# Mezz1.net
KiCad netlist of a schematic drawn in Altium Designer
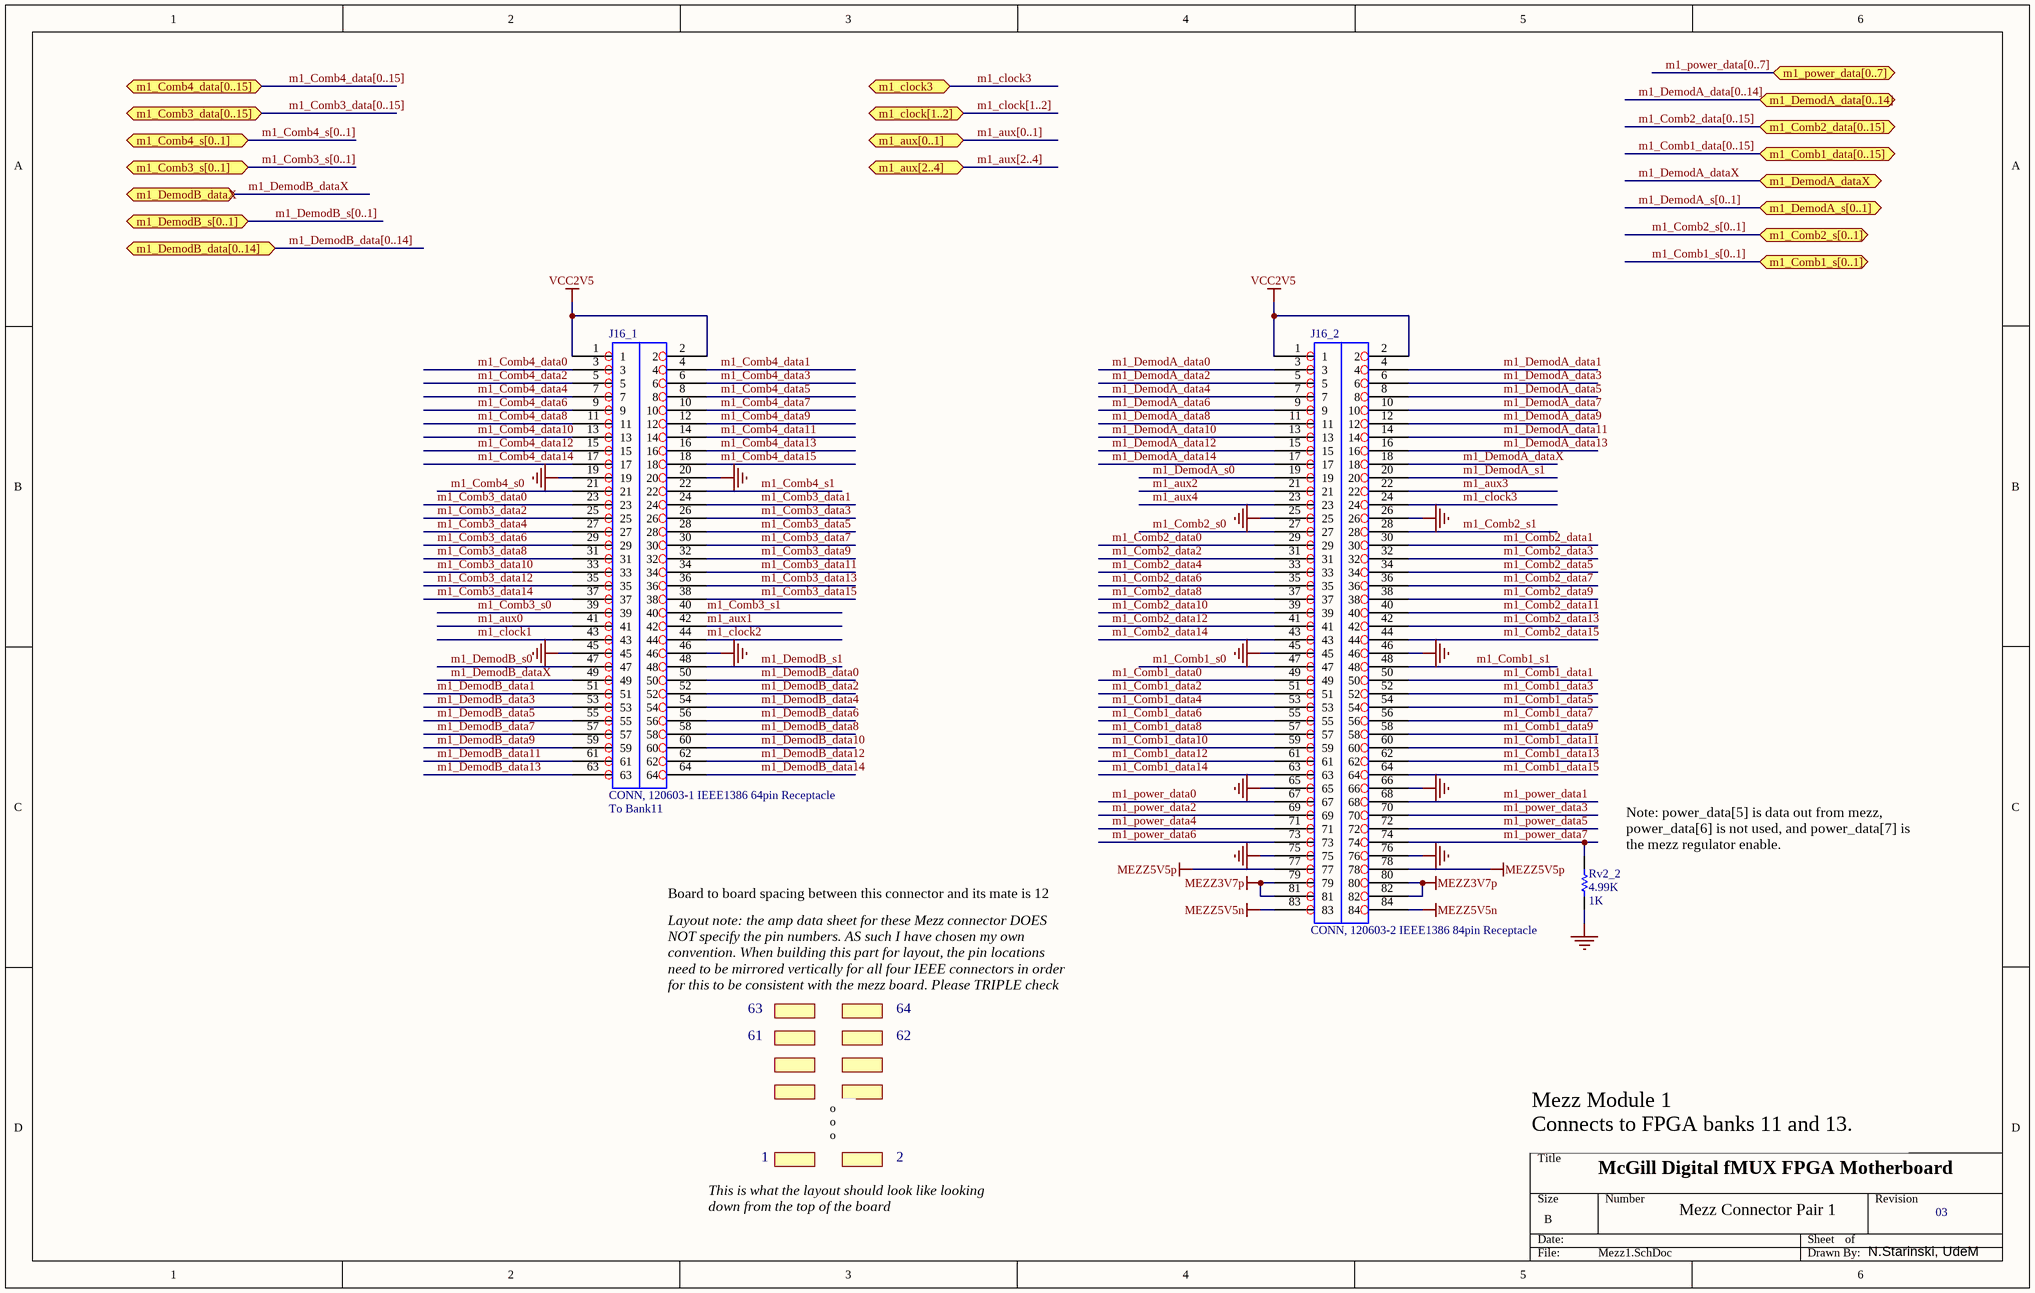
[diagram p0: Mezz1.SchDoc]

(export (version "E")
  (design (tool "Eeschema 10.0.6"))
  (components
    (comp (ref "J16_1")
      (value "CONN, 120603-1 IEEE1386 64pin Receptacle")
      (footprint "120603-1")
      (description "1.0mm FH (IEEE1386) 64-pin Connector")
      (fields (field (name "RELATION") "To Bank11"))
      (libsource (lib "IEEE1386") (part "120603-1"))
    )
    (comp (ref "J16_2")
      (value "CONN, 120603-2 IEEE1386 84pin Receptacle")
      (footprint "120603-2")
      (description "1.0mm FH (IEEE1386) 84-pin Connector")
      (libsource (lib "IEEE1386") (part "120603-2"))
    )
    (comp (ref "Rv2_2")
      (value "4.99K")
      (footprint "1608[0603]")
      (description "Semiconductor Resistor")
      (fields (field (name "ALTIUM_VALUE") "1K") (field (name "PUBLISHER") "Altium Limited"))
      (libsource (lib "Miscellaneous Devices") (part "Res Semi"))
    )
  )
  (nets
    (net (code "1") (name "/m1_Comb1_data0") (class "Default")
      (node (ref "J16_2") (pin "49") (pinfunction "49_49") (pintype "passive"))
    )
    (net (code "2") (name "/m1_Comb1_data1") (class "Default")
      (node (ref "J16_2") (pin "50") (pinfunction "50_50") (pintype "passive"))
    )
    (net (code "3") (name "/m1_Comb1_data2") (class "Default")
      (node (ref "J16_2") (pin "51") (pinfunction "51_51") (pintype "passive"))
    )
    (net (code "4") (name "/m1_Comb1_data3") (class "Default")
      (node (ref "J16_2") (pin "52") (pinfunction "52_52") (pintype "passive"))
    )
    (net (code "5") (name "/m1_Comb1_data4") (class "Default")
      (node (ref "J16_2") (pin "53") (pinfunction "53_53") (pintype "passive"))
    )
    (net (code "6") (name "/m1_Comb1_data5") (class "Default")
      (node (ref "J16_2") (pin "54") (pinfunction "54_54") (pintype "passive"))
    )
    (net (code "7") (name "/m1_Comb1_data6") (class "Default")
      (node (ref "J16_2") (pin "55") (pinfunction "55_55") (pintype "passive"))
    )
    (net (code "8") (name "/m1_Comb1_data7") (class "Default")
      (node (ref "J16_2") (pin "56") (pinfunction "56_56") (pintype "passive"))
    )
    (net (code "9") (name "/m1_Comb1_data8") (class "Default")
      (node (ref "J16_2") (pin "57") (pinfunction "57_57") (pintype "passive"))
    )
    (net (code "10") (name "/m1_Comb1_data9") (class "Default")
      (node (ref "J16_2") (pin "58") (pinfunction "58_58") (pintype "passive"))
    )
    (net (code "11") (name "/m1_Comb1_data10") (class "Default")
      (node (ref "J16_2") (pin "59") (pinfunction "59_59") (pintype "passive"))
    )
    (net (code "12") (name "/m1_Comb1_data11") (class "Default")
      (node (ref "J16_2") (pin "60") (pinfunction "60_60") (pintype "passive"))
    )
    (net (code "13") (name "/m1_Comb1_data12") (class "Default")
      (node (ref "J16_2") (pin "61") (pinfunction "61_61") (pintype "passive"))
    )
    (net (code "14") (name "/m1_Comb1_data13") (class "Default")
      (node (ref "J16_2") (pin "62") (pinfunction "62_62") (pintype "passive"))
    )
    (net (code "15") (name "/m1_Comb1_data14") (class "Default")
      (node (ref "J16_2") (pin "63") (pinfunction "63_63") (pintype "passive"))
    )
    (net (code "16") (name "/m1_Comb1_data15") (class "Default")
      (node (ref "J16_2") (pin "64") (pinfunction "64_64") (pintype "passive"))
    )
    (net (code "18") (name "/m1_Comb1_s0") (class "Default")
      (node (ref "J16_2") (pin "47") (pinfunction "47_47") (pintype "passive"))
    )
    (net (code "19") (name "/m1_Comb1_s1") (class "Default")
      (node (ref "J16_2") (pin "48") (pinfunction "48_48") (pintype "passive"))
    )
    (net (code "21") (name "/m1_Comb2_data0") (class "Default")
      (node (ref "J16_2") (pin "29") (pinfunction "29_29") (pintype "passive"))
    )
    (net (code "22") (name "/m1_Comb2_data1") (class "Default")
      (node (ref "J16_2") (pin "30") (pinfunction "30_30") (pintype "passive"))
    )
    (net (code "23") (name "/m1_Comb2_data2") (class "Default")
      (node (ref "J16_2") (pin "31") (pinfunction "31_31") (pintype "passive"))
    )
    (net (code "24") (name "/m1_Comb2_data3") (class "Default")
      (node (ref "J16_2") (pin "32") (pinfunction "32_32") (pintype "passive"))
    )
    (net (code "25") (name "/m1_Comb2_data4") (class "Default")
      (node (ref "J16_2") (pin "33") (pinfunction "33_33") (pintype "passive"))
    )
    (net (code "26") (name "/m1_Comb2_data5") (class "Default")
      (node (ref "J16_2") (pin "34") (pinfunction "34_34") (pintype "passive"))
    )
    (net (code "27") (name "/m1_Comb2_data6") (class "Default")
      (node (ref "J16_2") (pin "35") (pinfunction "35_35") (pintype "passive"))
    )
    (net (code "28") (name "/m1_Comb2_data7") (class "Default")
      (node (ref "J16_2") (pin "36") (pinfunction "36_36") (pintype "passive"))
    )
    (net (code "29") (name "/m1_Comb2_data8") (class "Default")
      (node (ref "J16_2") (pin "37") (pinfunction "37_37") (pintype "passive"))
    )
    (net (code "30") (name "/m1_Comb2_data9") (class "Default")
      (node (ref "J16_2") (pin "38") (pinfunction "38_38") (pintype "passive"))
    )
    (net (code "31") (name "/m1_Comb2_data10") (class "Default")
      (node (ref "J16_2") (pin "39") (pinfunction "39_39") (pintype "passive"))
    )
    (net (code "32") (name "/m1_Comb2_data11") (class "Default")
      (node (ref "J16_2") (pin "40") (pinfunction "40_40") (pintype "passive"))
    )
    (net (code "33") (name "/m1_Comb2_data12") (class "Default")
      (node (ref "J16_2") (pin "41") (pinfunction "41_41") (pintype "passive"))
    )
    (net (code "34") (name "/m1_Comb2_data13") (class "Default")
      (node (ref "J16_2") (pin "42") (pinfunction "42_42") (pintype "passive"))
    )
    (net (code "35") (name "/m1_Comb2_data14") (class "Default")
      (node (ref "J16_2") (pin "43") (pinfunction "43_43") (pintype "passive"))
    )
    (net (code "36") (name "/m1_Comb2_data15") (class "Default")
      (node (ref "J16_2") (pin "44") (pinfunction "44_44") (pintype "passive"))
    )
    (net (code "38") (name "/m1_Comb2_s0") (class "Default")
      (node (ref "J16_2") (pin "27") (pinfunction "27_27") (pintype "passive"))
    )
    (net (code "39") (name "/m1_Comb2_s1") (class "Default")
      (node (ref "J16_2") (pin "28") (pinfunction "28_28") (pintype "passive"))
    )
    (net (code "41") (name "/m1_Comb3_data0") (class "Default")
      (node (ref "J16_1") (pin "23") (pinfunction "23_23") (pintype "passive"))
    )
    (net (code "42") (name "/m1_Comb3_data1") (class "Default")
      (node (ref "J16_1") (pin "24") (pinfunction "24_24") (pintype "passive"))
    )
    (net (code "43") (name "/m1_Comb3_data2") (class "Default")
      (node (ref "J16_1") (pin "25") (pinfunction "25_25") (pintype "passive"))
    )
    (net (code "44") (name "/m1_Comb3_data3") (class "Default")
      (node (ref "J16_1") (pin "26") (pinfunction "26_26") (pintype "passive"))
    )
    (net (code "45") (name "/m1_Comb3_data4") (class "Default")
      (node (ref "J16_1") (pin "27") (pinfunction "27_27") (pintype "passive"))
    )
    (net (code "46") (name "/m1_Comb3_data5") (class "Default")
      (node (ref "J16_1") (pin "28") (pinfunction "28_28") (pintype "passive"))
    )
    (net (code "47") (name "/m1_Comb3_data6") (class "Default")
      (node (ref "J16_1") (pin "29") (pinfunction "29_29") (pintype "passive"))
    )
    (net (code "48") (name "/m1_Comb3_data7") (class "Default")
      (node (ref "J16_1") (pin "30") (pinfunction "30_30") (pintype "passive"))
    )
    (net (code "49") (name "/m1_Comb3_data8") (class "Default")
      (node (ref "J16_1") (pin "31") (pinfunction "31_31") (pintype "passive"))
    )
    (net (code "50") (name "/m1_Comb3_data9") (class "Default")
      (node (ref "J16_1") (pin "32") (pinfunction "32_32") (pintype "passive"))
    )
    (net (code "51") (name "/m1_Comb3_data10") (class "Default")
      (node (ref "J16_1") (pin "33") (pinfunction "33_33") (pintype "passive"))
    )
    (net (code "52") (name "/m1_Comb3_data11") (class "Default")
      (node (ref "J16_1") (pin "34") (pinfunction "34_34") (pintype "passive"))
    )
    (net (code "53") (name "/m1_Comb3_data12") (class "Default")
      (node (ref "J16_1") (pin "35") (pinfunction "35_35") (pintype "passive"))
    )
    (net (code "54") (name "/m1_Comb3_data13") (class "Default")
      (node (ref "J16_1") (pin "36") (pinfunction "36_36") (pintype "passive"))
    )
    (net (code "55") (name "/m1_Comb3_data14") (class "Default")
      (node (ref "J16_1") (pin "37") (pinfunction "37_37") (pintype "passive"))
    )
    (net (code "56") (name "/m1_Comb3_data15") (class "Default")
      (node (ref "J16_1") (pin "38") (pinfunction "38_38") (pintype "passive"))
    )
    (net (code "58") (name "/m1_Comb3_s0") (class "Default")
      (node (ref "J16_1") (pin "39") (pinfunction "39_39") (pintype "passive"))
    )
    (net (code "59") (name "/m1_Comb3_s1") (class "Default")
      (node (ref "J16_1") (pin "40") (pinfunction "40_40") (pintype "passive"))
    )
    (net (code "61") (name "/m1_Comb4_data0") (class "Default")
      (node (ref "J16_1") (pin "3") (pinfunction "3_3") (pintype "passive"))
    )
    (net (code "62") (name "/m1_Comb4_data1") (class "Default")
      (node (ref "J16_1") (pin "4") (pinfunction "4_4") (pintype "passive"))
    )
    (net (code "63") (name "/m1_Comb4_data2") (class "Default")
      (node (ref "J16_1") (pin "5") (pinfunction "5_5") (pintype "passive"))
    )
    (net (code "64") (name "/m1_Comb4_data3") (class "Default")
      (node (ref "J16_1") (pin "6") (pinfunction "6_6") (pintype "passive"))
    )
    (net (code "65") (name "/m1_Comb4_data4") (class "Default")
      (node (ref "J16_1") (pin "7") (pinfunction "7_7") (pintype "passive"))
    )
    (net (code "66") (name "/m1_Comb4_data5") (class "Default")
      (node (ref "J16_1") (pin "8") (pinfunction "8_8") (pintype "passive"))
    )
    (net (code "67") (name "/m1_Comb4_data6") (class "Default")
      (node (ref "J16_1") (pin "9") (pinfunction "9_9") (pintype "passive"))
    )
    (net (code "68") (name "/m1_Comb4_data7") (class "Default")
      (node (ref "J16_1") (pin "10") (pinfunction "10_10") (pintype "passive"))
    )
    (net (code "69") (name "/m1_Comb4_data8") (class "Default")
      (node (ref "J16_1") (pin "11") (pinfunction "11_11") (pintype "passive"))
    )
    (net (code "70") (name "/m1_Comb4_data9") (class "Default")
      (node (ref "J16_1") (pin "12") (pinfunction "12_12") (pintype "passive"))
    )
    (net (code "71") (name "/m1_Comb4_data10") (class "Default")
      (node (ref "J16_1") (pin "13") (pinfunction "13_13") (pintype "passive"))
    )
    (net (code "72") (name "/m1_Comb4_data11") (class "Default")
      (node (ref "J16_1") (pin "14") (pinfunction "14_14") (pintype "passive"))
    )
    (net (code "73") (name "/m1_Comb4_data12") (class "Default")
      (node (ref "J16_1") (pin "15") (pinfunction "15_15") (pintype "passive"))
    )
    (net (code "74") (name "/m1_Comb4_data13") (class "Default")
      (node (ref "J16_1") (pin "16") (pinfunction "16_16") (pintype "passive"))
    )
    (net (code "75") (name "/m1_Comb4_data14") (class "Default")
      (node (ref "J16_1") (pin "17") (pinfunction "17_17") (pintype "passive"))
    )
    (net (code "76") (name "/m1_Comb4_data15") (class "Default")
      (node (ref "J16_1") (pin "18") (pinfunction "18_18") (pintype "passive"))
    )
    (net (code "78") (name "/m1_Comb4_s0") (class "Default")
      (node (ref "J16_1") (pin "21") (pinfunction "21_21") (pintype "passive"))
    )
    (net (code "79") (name "/m1_Comb4_s1") (class "Default")
      (node (ref "J16_1") (pin "22") (pinfunction "22_22") (pintype "passive"))
    )
    (net (code "81") (name "/m1_DemodA_data0") (class "Default")
      (node (ref "J16_2") (pin "3") (pinfunction "3_3") (pintype "passive"))
    )
    (net (code "82") (name "/m1_DemodA_data1") (class "Default")
      (node (ref "J16_2") (pin "4") (pinfunction "4_4") (pintype "passive"))
    )
    (net (code "83") (name "/m1_DemodA_data2") (class "Default")
      (node (ref "J16_2") (pin "5") (pinfunction "5_5") (pintype "passive"))
    )
    (net (code "84") (name "/m1_DemodA_data3") (class "Default")
      (node (ref "J16_2") (pin "6") (pinfunction "6_6") (pintype "passive"))
    )
    (net (code "85") (name "/m1_DemodA_data4") (class "Default")
      (node (ref "J16_2") (pin "7") (pinfunction "7_7") (pintype "passive"))
    )
    (net (code "86") (name "/m1_DemodA_data5") (class "Default")
      (node (ref "J16_2") (pin "8") (pinfunction "8_8") (pintype "passive"))
    )
    (net (code "87") (name "/m1_DemodA_data6") (class "Default")
      (node (ref "J16_2") (pin "9") (pinfunction "9_9") (pintype "passive"))
    )
    (net (code "88") (name "/m1_DemodA_data7") (class "Default")
      (node (ref "J16_2") (pin "10") (pinfunction "10_10") (pintype "passive"))
    )
    (net (code "89") (name "/m1_DemodA_data8") (class "Default")
      (node (ref "J16_2") (pin "11") (pinfunction "11_11") (pintype "passive"))
    )
    (net (code "90") (name "/m1_DemodA_data9") (class "Default")
      (node (ref "J16_2") (pin "12") (pinfunction "12_12") (pintype "passive"))
    )
    (net (code "91") (name "/m1_DemodA_data10") (class "Default")
      (node (ref "J16_2") (pin "13") (pinfunction "13_13") (pintype "passive"))
    )
    (net (code "92") (name "/m1_DemodA_data11") (class "Default")
      (node (ref "J16_2") (pin "14") (pinfunction "14_14") (pintype "passive"))
    )
    (net (code "93") (name "/m1_DemodA_data12") (class "Default")
      (node (ref "J16_2") (pin "15") (pinfunction "15_15") (pintype "passive"))
    )
    (net (code "94") (name "/m1_DemodA_data13") (class "Default")
      (node (ref "J16_2") (pin "16") (pinfunction "16_16") (pintype "passive"))
    )
    (net (code "95") (name "/m1_DemodA_data14") (class "Default")
      (node (ref "J16_2") (pin "17") (pinfunction "17_17") (pintype "passive"))
    )
    (net (code "96") (name "/m1_DemodA_dataX") (class "Default")
      (node (ref "J16_2") (pin "18") (pinfunction "18_18") (pintype "passive"))
    )
    (net (code "98") (name "/m1_DemodA_s0") (class "Default")
      (node (ref "J16_2") (pin "19") (pinfunction "19_19") (pintype "passive"))
    )
    (net (code "99") (name "/m1_DemodA_s1") (class "Default")
      (node (ref "J16_2") (pin "20") (pinfunction "20_20") (pintype "passive"))
    )
    (net (code "101") (name "/m1_DemodB_data0") (class "Default")
      (node (ref "J16_1") (pin "50") (pinfunction "50_50") (pintype "passive"))
    )
    (net (code "102") (name "/m1_DemodB_data1") (class "Default")
      (node (ref "J16_1") (pin "51") (pinfunction "51_51") (pintype "passive"))
    )
    (net (code "103") (name "/m1_DemodB_data2") (class "Default")
      (node (ref "J16_1") (pin "52") (pinfunction "52_52") (pintype "passive"))
    )
    (net (code "104") (name "/m1_DemodB_data3") (class "Default")
      (node (ref "J16_1") (pin "53") (pinfunction "53_53") (pintype "passive"))
    )
    (net (code "105") (name "/m1_DemodB_data4") (class "Default")
      (node (ref "J16_1") (pin "54") (pinfunction "54_54") (pintype "passive"))
    )
    (net (code "106") (name "/m1_DemodB_data5") (class "Default")
      (node (ref "J16_1") (pin "55") (pinfunction "55_55") (pintype "passive"))
    )
    (net (code "107") (name "/m1_DemodB_data6") (class "Default")
      (node (ref "J16_1") (pin "56") (pinfunction "56_56") (pintype "passive"))
    )
    (net (code "108") (name "/m1_DemodB_data7") (class "Default")
      (node (ref "J16_1") (pin "57") (pinfunction "57_57") (pintype "passive"))
    )
    (net (code "109") (name "/m1_DemodB_data8") (class "Default")
      (node (ref "J16_1") (pin "58") (pinfunction "58_58") (pintype "passive"))
    )
    (net (code "110") (name "/m1_DemodB_data9") (class "Default")
      (node (ref "J16_1") (pin "59") (pinfunction "59_59") (pintype "passive"))
    )
    (net (code "111") (name "/m1_DemodB_data10") (class "Default")
      (node (ref "J16_1") (pin "60") (pinfunction "60_60") (pintype "passive"))
    )
    (net (code "112") (name "/m1_DemodB_data11") (class "Default")
      (node (ref "J16_1") (pin "61") (pinfunction "61_61") (pintype "passive"))
    )
    (net (code "113") (name "/m1_DemodB_data12") (class "Default")
      (node (ref "J16_1") (pin "62") (pinfunction "62_62") (pintype "passive"))
    )
    (net (code "114") (name "/m1_DemodB_data13") (class "Default")
      (node (ref "J16_1") (pin "63") (pinfunction "63_63") (pintype "passive"))
    )
    (net (code "115") (name "/m1_DemodB_data14") (class "Default")
      (node (ref "J16_1") (pin "64") (pinfunction "64_64") (pintype "passive"))
    )
    (net (code "116") (name "/m1_DemodB_dataX") (class "Default")
      (node (ref "J16_1") (pin "49") (pinfunction "49_49") (pintype "passive"))
    )
    (net (code "118") (name "/m1_DemodB_s0") (class "Default")
      (node (ref "J16_1") (pin "47") (pinfunction "47_47") (pintype "passive"))
    )
    (net (code "119") (name "/m1_DemodB_s1") (class "Default")
      (node (ref "J16_1") (pin "48") (pinfunction "48_48") (pintype "passive"))
    )
    (net (code "121") (name "/m1_aux0") (class "Default")
      (node (ref "J16_1") (pin "41") (pinfunction "41_41") (pintype "passive"))
    )
    (net (code "122") (name "/m1_aux1") (class "Default")
      (node (ref "J16_1") (pin "42") (pinfunction "42_42") (pintype "passive"))
    )
    (net (code "123") (name "/m1_aux2") (class "Default")
      (node (ref "J16_2") (pin "21") (pinfunction "21_21") (pintype "passive"))
    )
    (net (code "124") (name "/m1_aux3") (class "Default")
      (node (ref "J16_2") (pin "22") (pinfunction "22_22") (pintype "passive"))
    )
    (net (code "125") (name "/m1_aux4") (class "Default")
      (node (ref "J16_2") (pin "23") (pinfunction "23_23") (pintype "passive"))
    )
    (net (code "128") (name "/m1_clock1") (class "Default")
      (node (ref "J16_1") (pin "43") (pinfunction "43_43") (pintype "passive"))
    )
    (net (code "129") (name "/m1_clock2") (class "Default")
      (node (ref "J16_1") (pin "44") (pinfunction "44_44") (pintype "passive"))
    )
    (net (code "130") (name "/m1_clock3") (class "Default")
      (node (ref "J16_2") (pin "24") (pinfunction "24_24") (pintype "passive"))
    )
    (net (code "132") (name "/m1_power_data0") (class "Default")
      (node (ref "J16_2") (pin "67") (pinfunction "67_67") (pintype "passive"))
    )
    (net (code "133") (name "/m1_power_data1") (class "Default")
      (node (ref "J16_2") (pin "68") (pinfunction "68_68") (pintype "passive"))
    )
    (net (code "134") (name "/m1_power_data2") (class "Default")
      (node (ref "J16_2") (pin "69") (pinfunction "69_69") (pintype "passive"))
    )
    (net (code "135") (name "/m1_power_data3") (class "Default")
      (node (ref "J16_2") (pin "70") (pinfunction "70_70") (pintype "passive"))
    )
    (net (code "136") (name "/m1_power_data4") (class "Default")
      (node (ref "J16_2") (pin "71") (pinfunction "71_71") (pintype "passive"))
    )
    (net (code "137") (name "/m1_power_data5") (class "Default")
      (node (ref "J16_2") (pin "72") (pinfunction "72_72") (pintype "passive"))
    )
    (net (code "138") (name "/m1_power_data6") (class "Default")
      (node (ref "J16_2") (pin "73") (pinfunction "73_73") (pintype "passive"))
    )
    (net (code "139") (name "/m1_power_data7") (class "Default")
      (node (ref "J16_2") (pin "74") (pinfunction "74_74") (pintype "passive"))
      (node (ref "Rv2_2") (pin "2") (pinfunction "2_2") (pintype "passive"))
    )
    (net (code "141") (name "GND") (class "Default")
      (node (ref "J16_1") (pin "19") (pinfunction "19_19") (pintype "passive"))
      (node (ref "J16_1") (pin "20") (pinfunction "20_20") (pintype "passive"))
      (node (ref "J16_1") (pin "45") (pinfunction "45_45") (pintype "passive"))
      (node (ref "J16_1") (pin "46") (pinfunction "46_46") (pintype "passive"))
      (node (ref "J16_2") (pin "25") (pinfunction "25_25") (pintype "passive"))
      (node (ref "J16_2") (pin "26") (pinfunction "26_26") (pintype "passive"))
      (node (ref "J16_2") (pin "45") (pinfunction "45_45") (pintype "passive"))
      (node (ref "J16_2") (pin "46") (pinfunction "46_46") (pintype "passive"))
      (node (ref "J16_2") (pin "65") (pinfunction "65_65") (pintype "passive"))
      (node (ref "J16_2") (pin "66") (pinfunction "66_66") (pintype "passive"))
      (node (ref "J16_2") (pin "75") (pinfunction "75_75") (pintype "passive"))
      (node (ref "J16_2") (pin "76") (pinfunction "76_76") (pintype "passive"))
      (node (ref "Rv2_2") (pin "1") (pinfunction "1_1") (pintype "passive"))
    )
    (net (code "142") (name "MEZZ3V7p") (class "Default")
      (node (ref "J16_2") (pin "79") (pinfunction "79_79") (pintype "passive"))
      (node (ref "J16_2") (pin "80") (pinfunction "80_80") (pintype "passive"))
      (node (ref "J16_2") (pin "81") (pinfunction "81_81") (pintype "passive"))
      (node (ref "J16_2") (pin "82") (pinfunction "82_82") (pintype "passive"))
    )
    (net (code "143") (name "MEZZ5V5n") (class "Default")
      (node (ref "J16_2") (pin "83") (pinfunction "83_83") (pintype "passive"))
      (node (ref "J16_2") (pin "84") (pinfunction "84_84") (pintype "passive"))
    )
    (net (code "144") (name "MEZZ5V5p") (class "Default")
      (node (ref "J16_2") (pin "77") (pinfunction "77_77") (pintype "passive"))
      (node (ref "J16_2") (pin "78") (pinfunction "78_78") (pintype "passive"))
    )
    (net (code "145") (name "VCC2V5") (class "Default")
      (node (ref "J16_1") (pin "1") (pinfunction "1_1") (pintype "passive"))
      (node (ref "J16_1") (pin "2") (pinfunction "2_2") (pintype "passive"))
      (node (ref "J16_2") (pin "1") (pinfunction "1_1") (pintype "passive"))
      (node (ref "J16_2") (pin "2") (pinfunction "2_2") (pintype "passive"))
    )
  )
)
